# DMXmerger.net
KiCad netlist of a schematic drawn in EAGLE
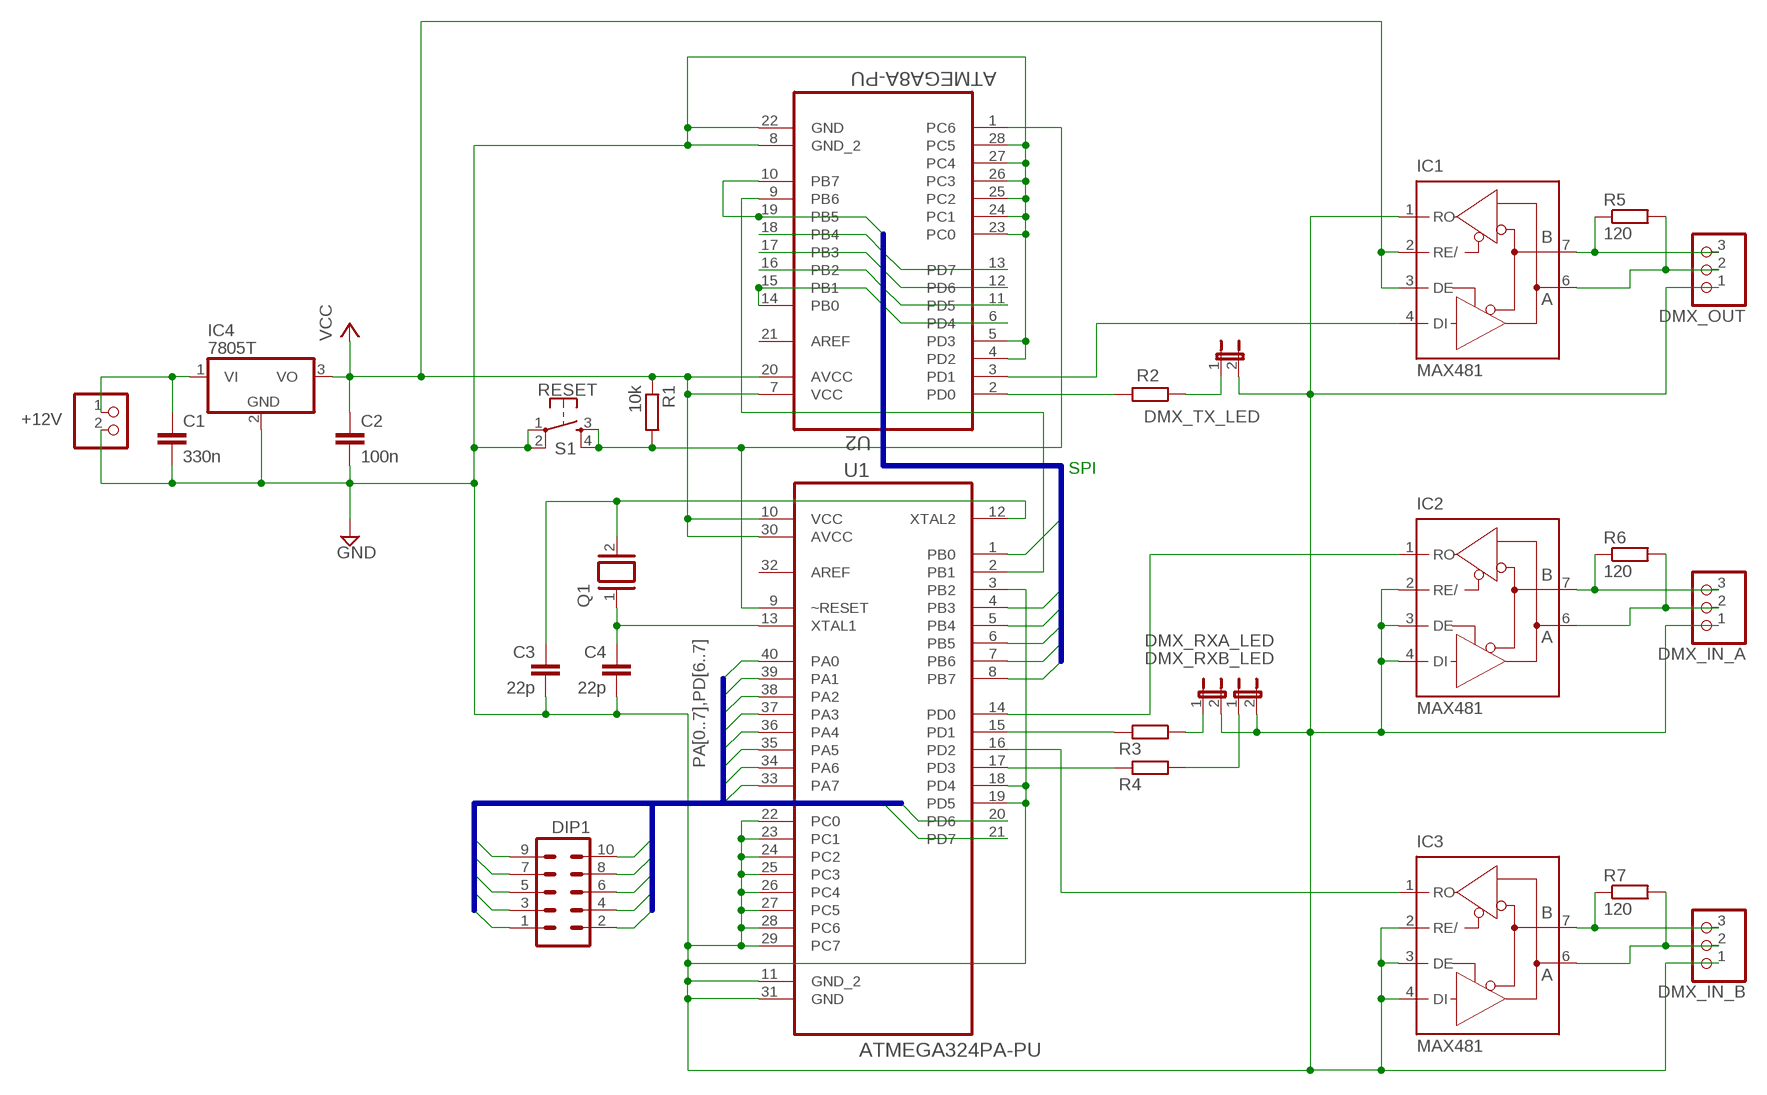
[diagram p0: schematic, sheet 1]

(export (version "E")
  (design (tool "Eeschema 10.0.6"))
  (components
    (comp (ref "+12V")
      (value "PINHD-1X2")
      (footprint "eagle-import:1X02")
      (libsource (lib "eagle-import") (part "PINHD-1X2"))
    )
    (comp (ref "C1")
      (value "330n")
      (footprint "eagle-import:C5B3")
      (libsource (lib "eagle-import") (part "C5/3"))
    )
    (comp (ref "C2")
      (value "100n")
      (footprint "eagle-import:C5B3")
      (libsource (lib "eagle-import") (part "C5/3"))
    )
    (comp (ref "C3")
      (value "22p")
      (footprint "eagle-import:C5B3")
      (libsource (lib "eagle-import") (part "C5/3"))
    )
    (comp (ref "C4")
      (value "22p")
      (footprint "eagle-import:C5B3")
      (libsource (lib "eagle-import") (part "C5/3"))
    )
    (comp (ref "DIP1")
      (value "MA05-2")
      (footprint "eagle-import:MA05-2")
      (libsource (lib "eagle-import") (part "MA05-2"))
    )
    (comp (ref "DMX_IN_A")
      (value "PINHD-1X3")
      (footprint "eagle-import:1X03")
      (libsource (lib "eagle-import") (part "PINHD-1X3"))
    )
    (comp (ref "DMX_IN_B")
      (value "PINHD-1X3")
      (footprint "eagle-import:1X03")
      (libsource (lib "eagle-import") (part "PINHD-1X3"))
    )
    (comp (ref "DMX_OUT")
      (value "PINHD-1X3")
      (footprint "eagle-import:1X03")
      (libsource (lib "eagle-import") (part "PINHD-1X3"))
    )
    (comp (ref "DMX_RXA_LED")
      (value "JP1E")
      (footprint "eagle-import:JP1")
      (libsource (lib "eagle-import") (part "JP1E"))
    )
    (comp (ref "DMX_RXB_LED")
      (value "JP1E")
      (footprint "eagle-import:JP1")
      (libsource (lib "eagle-import") (part "JP1E"))
    )
    (comp (ref "DMX_TX_LED")
      (value "JP1E")
      (footprint "eagle-import:JP1")
      (libsource (lib "eagle-import") (part "JP1E"))
    )
    (comp (ref "IC1")
      (value "MAX481")
      (footprint "eagle-import:DIL08")
      (fields (field (name "MPN") "MAX481CPA+"))
      (libsource (lib "eagle-import") (part "MAX481CPA"))
    )
    (comp (ref "IC2")
      (value "MAX481")
      (footprint "eagle-import:DIL08")
      (fields (field (name "MPN") "MAX481CPA+"))
      (libsource (lib "eagle-import") (part "MAX481CPA"))
    )
    (comp (ref "IC3")
      (value "MAX481")
      (footprint "eagle-import:DIL08")
      (fields (field (name "MPN") "MAX481CPA+"))
      (libsource (lib "eagle-import") (part "MAX481CPA"))
    )
    (comp (ref "IC4")
      (value "7805T")
      (footprint "eagle-import:TO220H")
      (libsource (lib "eagle-import") (part "78T05"))
    )
    (comp (ref "Q1")
      (value "XTAL/S")
      (footprint "eagle-import:QS")
      (libsource (lib "eagle-import") (part "XTAL/S"))
    )
    (comp (ref "R1")
      (value "10k")
      (footprint "eagle-import:0207_12")
      (libsource (lib "eagle-import") (part "R-EU_0207/12"))
    )
    (comp (ref "R2")
      (value "250")
      (footprint "eagle-import:0207_12")
      (libsource (lib "eagle-import") (part "R-EU_0207/12"))
    )
    (comp (ref "R3")
      (value "250")
      (footprint "eagle-import:0207_12")
      (libsource (lib "eagle-import") (part "R-EU_0207/12"))
    )
    (comp (ref "R4")
      (value "250")
      (footprint "eagle-import:0207_12")
      (libsource (lib "eagle-import") (part "R-EU_0207/12"))
    )
    (comp (ref "R5")
      (value "120")
      (footprint "eagle-import:0207_12")
      (libsource (lib "eagle-import") (part "R-EU_0207/12"))
    )
    (comp (ref "R6")
      (value "120")
      (footprint "eagle-import:0207_12")
      (libsource (lib "eagle-import") (part "R-EU_0207/12"))
    )
    (comp (ref "R7")
      (value "120")
      (footprint "eagle-import:0207_12")
      (libsource (lib "eagle-import") (part "R-EU_0207/12"))
    )
    (comp (ref "S1")
      (value "RESET")
      (footprint "eagle-import:DTS-6")
      (libsource (lib "eagle-import") (part "DTS-6"))
    )
    (comp (ref "U1")
      (value "ATMEGA324PA-PU")
      (footprint "eagle-import:DIP254P1524X482-40")
      (libsource (lib "eagle-import") (part "ATMEGA324PA-PU"))
    )
    (comp (ref "U2")
      (value "ATMEGA8A-PU")
      (footprint "eagle-import:DIP254P762X457-28")
      (libsource (lib "eagle-import") (part "ATMEGA8A-PU"))
    )
  )
  (nets
    (net (code "1") (name "/1") (class "Default")
      (node (ref "DIP1") (pin "1") (pinfunction "1_1") (pintype "passive"))
      (node (ref "U1") (pin "37") (pinfunction "PA3_37") (pintype "bidirectional"))
    )
    (net (code "2") (name "/2") (class "Default")
      (node (ref "DIP1") (pin "2") (pinfunction "2_2") (pintype "passive"))
      (node (ref "U1") (pin "38") (pinfunction "PA2_38") (pintype "bidirectional"))
    )
    (net (code "3") (name "/3") (class "Default")
      (node (ref "DIP1") (pin "3") (pinfunction "3_3") (pintype "passive"))
      (node (ref "U1") (pin "36") (pinfunction "PA4_36") (pintype "bidirectional"))
    )
    (net (code "4") (name "/4") (class "Default")
      (node (ref "DIP1") (pin "4") (pinfunction "4_4") (pintype "passive"))
      (node (ref "U1") (pin "39") (pinfunction "PA1_39") (pintype "bidirectional"))
    )
    (net (code "5") (name "/5") (class "Default")
      (node (ref "DIP1") (pin "5") (pinfunction "5_5") (pintype "passive"))
      (node (ref "U1") (pin "35") (pinfunction "PA5_35") (pintype "bidirectional"))
    )
    (net (code "6") (name "/6") (class "Default")
      (node (ref "DIP1") (pin "6") (pinfunction "6_6") (pintype "passive"))
      (node (ref "U1") (pin "40") (pinfunction "PA0_40") (pintype "bidirectional"))
    )
    (net (code "7") (name "/7") (class "Default")
      (node (ref "DIP1") (pin "7") (pinfunction "7_7") (pintype "passive"))
      (node (ref "U1") (pin "34") (pinfunction "PA6_34") (pintype "bidirectional"))
    )
    (net (code "8") (name "/8") (class "Default")
      (node (ref "DIP1") (pin "8") (pinfunction "8_8") (pintype "passive"))
      (node (ref "U1") (pin "20") (pinfunction "PD6_20") (pintype "bidirectional"))
    )
    (net (code "9") (name "/10") (class "Default")
      (node (ref "DIP1") (pin "10") (pinfunction "10_10") (pintype "passive"))
      (node (ref "U1") (pin "21") (pinfunction "PD7_21") (pintype "bidirectional"))
    )
    (net (code "10") (name "/LED") (class "Default")
      (node (ref "U1") (pin "1") (pinfunction "PB0_1") (pintype "bidirectional"))
      (node (ref "U2") (pin "6") (pinfunction "PD4_6") (pintype "bidirectional"))
    )
    (net (code "11") (name "/MISO") (class "Default")
      (node (ref "U1") (pin "7") (pinfunction "PB6_7") (pintype "bidirectional"))
      (node (ref "U2") (pin "11") (pinfunction "PD5_11") (pintype "bidirectional"))
      (node (ref "U2") (pin "18") (pinfunction "PB4_18") (pintype "bidirectional"))
    )
    (net (code "12") (name "/MOSI") (class "Default")
      (node (ref "U1") (pin "6") (pinfunction "PB5_6") (pintype "bidirectional"))
      (node (ref "U2") (pin "12") (pinfunction "PD6_12") (pintype "bidirectional"))
      (node (ref "U2") (pin "17") (pinfunction "PB3_17") (pintype "bidirectional"))
    )
    (net (code "13") (name "/PA0") (class "Default")
      (node (ref "DIP1") (pin "9") (pinfunction "9_9") (pintype "passive"))
      (node (ref "U1") (pin "33") (pinfunction "PA7_33") (pintype "bidirectional"))
    )
    (net (code "14") (name "/RST") (class "Default")
      (node (ref "U1") (pin "4") (pinfunction "PB3_4") (pintype "bidirectional"))
      (node (ref "U2") (pin "14") (pinfunction "PB0_14") (pintype "bidirectional"))
      (node (ref "U2") (pin "15") (pinfunction "PB1_15") (pintype "bidirectional"))
    )
    (net (code "15") (name "/SCK") (class "Default")
      (node (ref "U1") (pin "8") (pinfunction "PB7_8") (pintype "bidirectional"))
      (node (ref "U2") (pin "10") (pinfunction "PB7_10") (pintype "bidirectional"))
      (node (ref "U2") (pin "19") (pinfunction "PB5_19") (pintype "bidirectional"))
    )
    (net (code "16") (name "/SS") (class "Default")
      (node (ref "U1") (pin "5") (pinfunction "PB4_5") (pintype "bidirectional"))
      (node (ref "U2") (pin "13") (pinfunction "PD7_13") (pintype "bidirectional"))
      (node (ref "U2") (pin "16") (pinfunction "PB2_16") (pintype "bidirectional"))
    )
    (net (code "18") (name "GND") (class "Default")
      (node (ref "+12V") (pin "2") (pinfunction "2_2") (pintype "passive"))
      (node (ref "C1") (pin "2") (pinfunction "2_2") (pintype "passive"))
      (node (ref "C2") (pin "2") (pinfunction "2_2") (pintype "passive"))
      (node (ref "C3") (pin "2") (pinfunction "2_2") (pintype "passive"))
      (node (ref "C4") (pin "2") (pinfunction "2_2") (pintype "passive"))
      (node (ref "DMX_IN_A") (pin "1") (pinfunction "1_1") (pintype "passive"))
      (node (ref "DMX_IN_B") (pin "1") (pinfunction "1_1") (pintype "passive"))
      (node (ref "DMX_OUT") (pin "1") (pinfunction "1_1") (pintype "passive"))
      (node (ref "DMX_RXA_LED") (pin "2") (pinfunction "2_2") (pintype "passive"))
      (node (ref "DMX_RXB_LED") (pin "2") (pinfunction "2_2") (pintype "passive"))
      (node (ref "DMX_TX_LED") (pin "2") (pinfunction "2_2") (pintype "passive"))
      (node (ref "IC1") (pin "1") (pinfunction "RO_1") (pintype "output"))
      (node (ref "IC2") (pin "2") (pinfunction "RE/_2") (pintype "input"))
      (node (ref "IC2") (pin "3") (pinfunction "DE_3") (pintype "input"))
      (node (ref "IC2") (pin "4") (pinfunction "DI_4") (pintype "input"))
      (node (ref "IC3") (pin "2") (pinfunction "RE/_2") (pintype "input"))
      (node (ref "IC3") (pin "3") (pinfunction "DE_3") (pintype "input"))
      (node (ref "IC3") (pin "4") (pinfunction "DI_4") (pintype "input"))
      (node (ref "IC4") (pin "2") (pinfunction "GND_2") (pintype "passive"))
      (node (ref "S1") (pin "1") (pinfunction "1_1") (pintype "passive"))
      (node (ref "S1") (pin "2") (pinfunction "2_2") (pintype "passive"))
      (node (ref "U1") (pin "11") (pinfunction "GND_2_11") (pintype "passive"))
      (node (ref "U1") (pin "18") (pinfunction "PD4_18") (pintype "bidirectional"))
      (node (ref "U1") (pin "19") (pinfunction "PD5_19") (pintype "bidirectional"))
      (node (ref "U1") (pin "22") (pinfunction "PC0_22") (pintype "bidirectional"))
      (node (ref "U1") (pin "23") (pinfunction "PC1_23") (pintype "bidirectional"))
      (node (ref "U1") (pin "24") (pinfunction "PC2_24") (pintype "bidirectional"))
      (node (ref "U1") (pin "25") (pinfunction "PC3_25") (pintype "bidirectional"))
      (node (ref "U1") (pin "26") (pinfunction "PC4_26") (pintype "bidirectional"))
      (node (ref "U1") (pin "27") (pinfunction "PC5_27") (pintype "bidirectional"))
      (node (ref "U1") (pin "28") (pinfunction "PC6_28") (pintype "bidirectional"))
      (node (ref "U1") (pin "29") (pinfunction "PC7_29") (pintype "bidirectional"))
      (node (ref "U1") (pin "3") (pinfunction "PB2_3") (pintype "bidirectional"))
      (node (ref "U1") (pin "31") (pinfunction "GND_31") (pintype "passive"))
      (node (ref "U2") (pin "22") (pinfunction "GND_22") (pintype "passive"))
      (node (ref "U2") (pin "23") (pinfunction "PC0_23") (pintype "bidirectional"))
      (node (ref "U2") (pin "24") (pinfunction "PC1_24") (pintype "bidirectional"))
      (node (ref "U2") (pin "25") (pinfunction "PC2_25") (pintype "bidirectional"))
      (node (ref "U2") (pin "26") (pinfunction "PC3_26") (pintype "bidirectional"))
      (node (ref "U2") (pin "27") (pinfunction "PC4_27") (pintype "bidirectional"))
      (node (ref "U2") (pin "28") (pinfunction "PC5_28") (pintype "bidirectional"))
      (node (ref "U2") (pin "4") (pinfunction "PD2_4") (pintype "bidirectional"))
      (node (ref "U2") (pin "5") (pinfunction "PD3_5") (pintype "bidirectional"))
      (node (ref "U2") (pin "8") (pinfunction "GND_2_8") (pintype "passive"))
    )
    (net (code "19") (name "Net-(DMX_RXA_LED-Pad1)") (class "Default")
      (node (ref "DMX_RXA_LED") (pin "1") (pinfunction "1_1") (pintype "passive"))
      (node (ref "R3") (pin "1") (pinfunction "1_1") (pintype "passive"))
    )
    (net (code "20") (name "Net-(DMX_RXB_LED-Pad1)") (class "Default")
      (node (ref "DMX_RXB_LED") (pin "1") (pinfunction "1_1") (pintype "passive"))
      (node (ref "R4") (pin "1") (pinfunction "1_1") (pintype "passive"))
    )
    (net (code "21") (name "Net-(DMX_TX_LED-Pad1)") (class "Default")
      (node (ref "DMX_TX_LED") (pin "1") (pinfunction "1_1") (pintype "passive"))
      (node (ref "R2") (pin "1") (pinfunction "1_1") (pintype "passive"))
    )
    (net (code "22") (name "Net-(IC1A-A)") (class "Default")
      (node (ref "DMX_OUT") (pin "2") (pinfunction "2_2") (pintype "passive"))
      (node (ref "IC1") (pin "6") (pinfunction "A_6") (pintype "passive"))
      (node (ref "R5") (pin "2") (pinfunction "2_2") (pintype "passive"))
    )
    (net (code "23") (name "Net-(IC1A-B)") (class "Default")
      (node (ref "DMX_OUT") (pin "3") (pinfunction "3_3") (pintype "passive"))
      (node (ref "IC1") (pin "7") (pinfunction "B_7") (pintype "passive"))
      (node (ref "R5") (pin "1") (pinfunction "1_1") (pintype "passive"))
    )
    (net (code "24") (name "Net-(IC1A-DI)") (class "Default")
      (node (ref "IC1") (pin "4") (pinfunction "DI_4") (pintype "input"))
      (node (ref "U2") (pin "3") (pinfunction "PD1_3") (pintype "bidirectional"))
    )
    (net (code "25") (name "Net-(IC2A-A)") (class "Default")
      (node (ref "DMX_IN_A") (pin "2") (pinfunction "2_2") (pintype "passive"))
      (node (ref "IC2") (pin "6") (pinfunction "A_6") (pintype "passive"))
      (node (ref "R6") (pin "2") (pinfunction "2_2") (pintype "passive"))
    )
    (net (code "26") (name "Net-(IC2A-B)") (class "Default")
      (node (ref "DMX_IN_A") (pin "3") (pinfunction "3_3") (pintype "passive"))
      (node (ref "IC2") (pin "7") (pinfunction "B_7") (pintype "passive"))
      (node (ref "R6") (pin "1") (pinfunction "1_1") (pintype "passive"))
    )
    (net (code "27") (name "Net-(IC2A-RO)") (class "Default")
      (node (ref "IC2") (pin "1") (pinfunction "RO_1") (pintype "output"))
      (node (ref "U1") (pin "14") (pinfunction "PD0_14") (pintype "bidirectional"))
    )
    (net (code "28") (name "Net-(IC3A-A)") (class "Default")
      (node (ref "DMX_IN_B") (pin "2") (pinfunction "2_2") (pintype "passive"))
      (node (ref "IC3") (pin "6") (pinfunction "A_6") (pintype "passive"))
      (node (ref "R7") (pin "2") (pinfunction "2_2") (pintype "passive"))
    )
    (net (code "29") (name "Net-(IC3A-B)") (class "Default")
      (node (ref "DMX_IN_B") (pin "3") (pinfunction "3_3") (pintype "passive"))
      (node (ref "IC3") (pin "7") (pinfunction "B_7") (pintype "passive"))
      (node (ref "R7") (pin "1") (pinfunction "1_1") (pintype "passive"))
    )
    (net (code "30") (name "Net-(IC3A-RO)") (class "Default")
      (node (ref "IC3") (pin "1") (pinfunction "RO_1") (pintype "output"))
      (node (ref "U1") (pin "16") (pinfunction "PD2_16") (pintype "bidirectional"))
    )
    (net (code "31") (name "Net-(IC4-VI)") (class "Default")
      (node (ref "+12V") (pin "1") (pinfunction "1_1") (pintype "passive"))
      (node (ref "C1") (pin "1") (pinfunction "1_1") (pintype "passive"))
      (node (ref "IC4") (pin "1") (pinfunction "VI_1") (pintype "input"))
    )
    (net (code "32") (name "Net-(U1-PB1)") (class "Default")
      (node (ref "U1") (pin "2") (pinfunction "PB1_2") (pintype "bidirectional"))
      (node (ref "U2") (pin "9") (pinfunction "PB6_9") (pintype "bidirectional"))
    )
    (net (code "33") (name "Net-(U1-PD1)") (class "Default")
      (node (ref "R3") (pin "2") (pinfunction "2_2") (pintype "passive"))
      (node (ref "U1") (pin "15") (pinfunction "PD1_15") (pintype "bidirectional"))
    )
    (net (code "34") (name "Net-(U1-PD3)") (class "Default")
      (node (ref "R4") (pin "2") (pinfunction "2_2") (pintype "passive"))
      (node (ref "U1") (pin "17") (pinfunction "PD3_17") (pintype "bidirectional"))
    )
    (net (code "35") (name "Net-(U1-XTAL1)") (class "Default")
      (node (ref "C4") (pin "1") (pinfunction "1_1") (pintype "passive"))
      (node (ref "Q1") (pin "1") (pinfunction "1_1") (pintype "passive"))
      (node (ref "U1") (pin "13") (pinfunction "XTAL1_13") (pintype "input"))
    )
    (net (code "36") (name "Net-(U1-XTAL2)") (class "Default")
      (node (ref "C3") (pin "1") (pinfunction "1_1") (pintype "passive"))
      (node (ref "Q1") (pin "2") (pinfunction "2_2") (pintype "passive"))
      (node (ref "U1") (pin "12") (pinfunction "XTAL2_12") (pintype "output"))
    )
    (net (code "37") (name "Net-(U1-~{RESET})") (class "Default")
      (node (ref "R1") (pin "2") (pinfunction "2_2") (pintype "passive"))
      (node (ref "S1") (pin "3") (pinfunction "3_3") (pintype "passive"))
      (node (ref "S1") (pin "4") (pinfunction "4_4") (pintype "passive"))
      (node (ref "U1") (pin "9") (pinfunction "~{RESET}_9") (pintype "input"))
      (node (ref "U2") (pin "1") (pinfunction "PC6_1") (pintype "bidirectional"))
    )
    (net (code "38") (name "Net-(U2-PD0)") (class "Default")
      (node (ref "R2") (pin "2") (pinfunction "2_2") (pintype "passive"))
      (node (ref "U2") (pin "2") (pinfunction "PD0_2") (pintype "bidirectional"))
    )
    (net (code "39") (name "VCC") (class "Default")
      (node (ref "C2") (pin "1") (pinfunction "1_1") (pintype "passive"))
      (node (ref "IC1") (pin "2") (pinfunction "RE/_2") (pintype "input"))
      (node (ref "IC1") (pin "3") (pinfunction "DE_3") (pintype "input"))
      (node (ref "IC4") (pin "3") (pinfunction "VO_3") (pintype "passive"))
      (node (ref "R1") (pin "1") (pinfunction "1_1") (pintype "passive"))
      (node (ref "U1") (pin "10") (pinfunction "VCC_10") (pintype "power_in"))
      (node (ref "U1") (pin "30") (pinfunction "AVCC_30") (pintype "power_in"))
      (node (ref "U2") (pin "20") (pinfunction "AVCC_20") (pintype "power_in"))
      (node (ref "U2") (pin "7") (pinfunction "VCC_7") (pintype "power_in"))
    )
    (net (code "40") (name "unconnected-(U1-AREF-Pad32)") (class "Default")
      (node (ref "U1") (pin "32") (pinfunction "AREF_32") (pintype "input"))
    )
    (net (code "41") (name "unconnected-(U2-AREF-Pad21)") (class "Default")
      (node (ref "U2") (pin "21") (pinfunction "AREF_21") (pintype "input"))
    )
  )
)
